# PWM_Controller_Half_Bridge_V2.net
KiCad netlist of a schematic drawn in Altium Designer
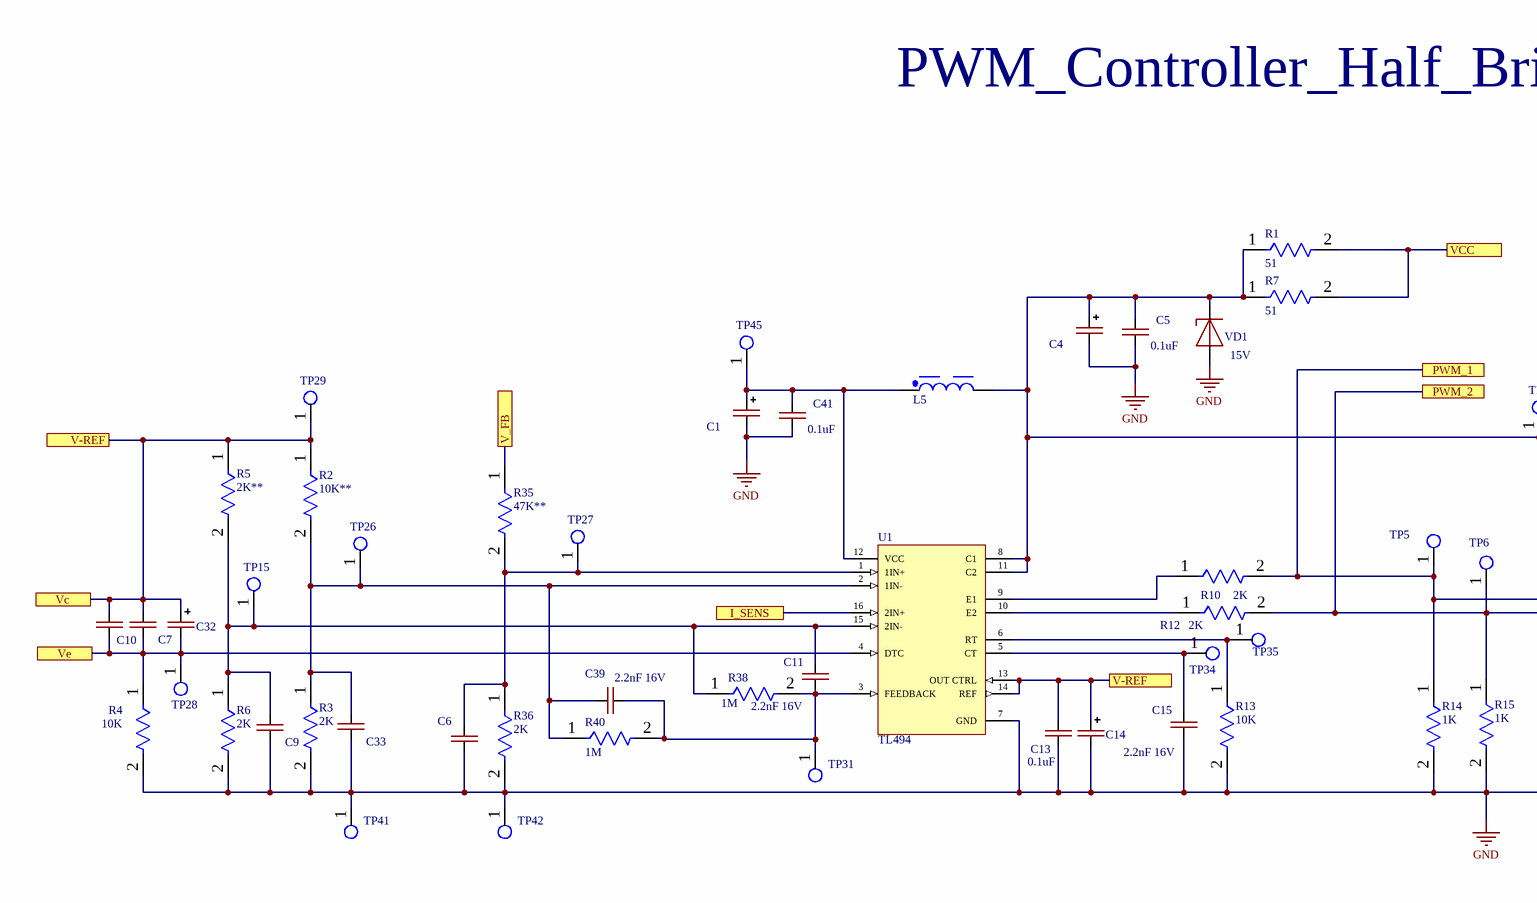
[diagram p0: PWM_Controller_Half_Bridge_V2.SchDoc, left]
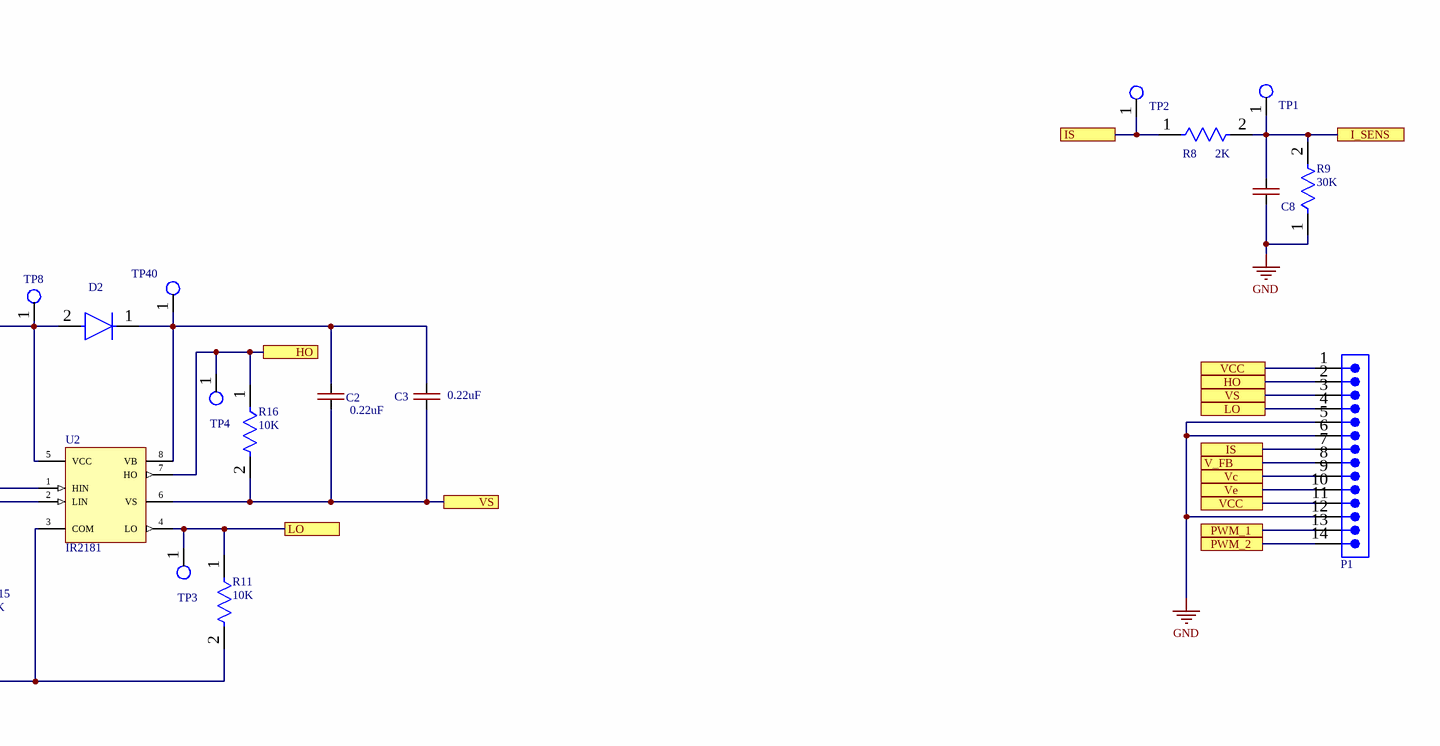
[diagram p1: PWM_Controller_Half_Bridge_V2.SchDoc, right]

(export (version "E")
  (design (tool "Eeschema 10.0.6"))
  (components
    (comp (ref "C1")
      (value "CAP-POLAR")
      (footprint "SIZE_EEE")
      (libsource (lib "PASSIVE_COMPONENTS") (part "CAP-POLAR"))
    )
    (comp (ref "C2")
      (value "0.22uF")
      (footprint "FP-C1210X475K5RACTU-IPC_C")
      (libsource (lib "PASSIVE_COMPONENTS") (part "CAP_1210"))
    )
    (comp (ref "C3")
      (value "0.22uF")
      (footprint "FP-C1210X475K5RACTU-IPC_C")
      (libsource (lib "PASSIVE_COMPONENTS") (part "CAP_1210"))
    )
    (comp (ref "C4")
      (value "CAP-POLAR")
      (footprint "SIZE_EEE")
      (libsource (lib "PASSIVE_COMPONENTS") (part "CAP-POLAR"))
    )
    (comp (ref "C5")
      (value "0.1uF")
      (footprint "CAP-0805")
      (libsource (lib "PASSIVE_COMPONENTS") (part "CAP-NON-POLAR"))
    )
    (comp (ref "C6")
      (value "CAP-NON-POLAR")
      (footprint "CAP-0805")
      (libsource (lib "PASSIVE_COMPONENTS") (part "CAP-NON-POLAR"))
    )
    (comp (ref "C7")
      (value "CAP-NON-POLAR")
      (footprint "CAP-0805")
      (libsource (lib "PASSIVE_COMPONENTS") (part "CAP-NON-POLAR"))
    )
    (comp (ref "C8")
      (value "CAP-NON-POLAR")
      (footprint "CAP-0805")
      (libsource (lib "PASSIVE_COMPONENTS") (part "CAP-NON-POLAR"))
    )
    (comp (ref "C9")
      (value "CAP-NON-POLAR")
      (footprint "CAP-0805")
      (libsource (lib "PASSIVE_COMPONENTS") (part "CAP-NON-POLAR"))
    )
    (comp (ref "C10")
      (value "CAP-NON-POLAR")
      (footprint "CAP-0805")
      (libsource (lib "PASSIVE_COMPONENTS") (part "CAP-NON-POLAR"))
    )
    (comp (ref "C11")
      (value "2.2nF 16V")
      (footprint "CAP-0805")
      (libsource (lib "PASSIVE_COMPONENTS") (part "CAP-NON-POLAR"))
    )
    (comp (ref "C13")
      (value "0.1uF")
      (footprint "CAP-0805")
      (libsource (lib "PASSIVE_COMPONENTS") (part "CAP-NON-POLAR"))
    )
    (comp (ref "C14")
      (value "CAP-POLAR")
      (footprint "CAP-TAN-D")
      (libsource (lib "PASSIVE_COMPONENTS") (part "CAP-POLAR"))
    )
    (comp (ref "C15")
      (value "2.2nF 16V")
      (footprint "CAP-0805")
      (libsource (lib "PASSIVE_COMPONENTS") (part "CAP-NON-POLAR"))
    )
    (comp (ref "C32")
      (value "CAP-POLAR")
      (footprint "CAP-TAN-D")
      (libsource (lib "PASSIVE_COMPONENTS") (part "CAP-POLAR"))
    )
    (comp (ref "C33")
      (value "CAP-NON-POLAR")
      (footprint "CAP-0805")
      (libsource (lib "PASSIVE_COMPONENTS") (part "CAP-NON-POLAR"))
    )
    (comp (ref "C39")
      (value "2.2nF 16V")
      (footprint "CAP-0805")
      (libsource (lib "PASSIVE_COMPONENTS") (part "CAP-NON-POLAR"))
    )
    (comp (ref "C41")
      (value "0.1uF")
      (footprint "CAP-0805")
      (libsource (lib "PASSIVE_COMPONENTS") (part "CAP-NON-POLAR"))
    )
    (comp (ref "D2") (value "US1G") (footprint "DO-214AA") (libsource (lib "Diodes") (part "US1G")))
    (comp (ref "L5")
      (value "47µH, 1.17A")
      (footprint "WE-PD2_7850")
      (description "WE-PD2 SMT Power Inductor, size 7850, 47µH, 1.17A, 0.18Ω")
      (fields
        (field (name "MANUFACTURER PART NUMBER") "744775147")
        (field (name "MANUFACTURER") "Wurth Elektronik")
      )
      (libsource (lib "WE-PD2 (rev22d)") (part "744775147"))
    )
    (comp (ref "P1")
      (value "61301411021")
      (footprint "61301411021")
      (description "WR-PHD Pin Header, THT, Angled, pitch 2.54mm, 1 Row, 14P")
      (fields (field (name "MANUFACTURER") "Wurth Elektronik"))
      (libsource (lib "Altium_WR-PHD (rev22b)") (part "61301411021"))
    )
    (comp (ref "R1")
      (value "51")
      (footprint "FP-RMCF1210-MFG")
      (description "51Ω ±5% 0.5W 1210 Thick Film Chip Resistor AEC-Q200 compliant")
      (fields (field (name "TOLERANCE") "5%"))
      (libsource (lib "Altium Content Vault") (part "1029c3af85768c4190bb7ad29bc67b5"))
    )
    (comp (ref "R2")
      (value "10K**")
      (footprint "RES-0805")
      (description "10K")
      (libsource (lib "PASSIVE_COMPONENTS") (part "RES-CONST"))
    )
    (comp (ref "R3")
      (value "2K")
      (footprint "RES-0805")
      (libsource (lib "PASSIVE_COMPONENTS") (part "RES-CONST"))
    )
    (comp (ref "R4")
      (value "10K")
      (footprint "RES-0805")
      (libsource (lib "PASSIVE_COMPONENTS") (part "RES-CONST"))
    )
    (comp (ref "R5")
      (value "2K**")
      (footprint "RES-0805")
      (description "2K")
      (libsource (lib "PASSIVE_COMPONENTS") (part "RES-CONST"))
    )
    (comp (ref "R6")
      (value "2K")
      (footprint "RES-0805")
      (libsource (lib "PASSIVE_COMPONENTS") (part "RES-CONST"))
    )
    (comp (ref "R7")
      (value "51")
      (footprint "FP-RMCF1210-MFG")
      (description "51Ω ±5% 0.5W 1210 Thick Film Chip Resistor AEC-Q200 compliant")
      (fields (field (name "TOLERANCE") "5%"))
      (libsource (lib "Altium Content Vault") (part "1029c3af85768c4190bb7ad29bc67b5"))
    )
    (comp (ref "R8")
      (value "2K")
      (footprint "RES-0805")
      (libsource (lib "PASSIVE_COMPONENTS") (part "RES-CONST"))
    )
    (comp (ref "R9")
      (value "30K")
      (footprint "RES-0805")
      (libsource (lib "PASSIVE_COMPONENTS") (part "RES-CONST"))
    )
    (comp (ref "R10")
      (value "2K")
      (footprint "RES-0805")
      (libsource (lib "PASSIVE_COMPONENTS") (part "RES-CONST"))
    )
    (comp (ref "R11")
      (value "10K")
      (footprint "RES-0805")
      (libsource (lib "PASSIVE_COMPONENTS") (part "RES-CONST"))
    )
    (comp (ref "R12")
      (value "2K")
      (footprint "RES-0805")
      (libsource (lib "PASSIVE_COMPONENTS") (part "RES-CONST"))
    )
    (comp (ref "R13")
      (value "10K")
      (footprint "RES-0805")
      (libsource (lib "PASSIVE_COMPONENTS") (part "RES-CONST"))
    )
    (comp (ref "R14")
      (value "1K")
      (footprint "RES-0805")
      (libsource (lib "PASSIVE_COMPONENTS") (part "RES-CONST"))
    )
    (comp (ref "R15")
      (value "1K")
      (footprint "RES-0805")
      (libsource (lib "PASSIVE_COMPONENTS") (part "RES-CONST"))
    )
    (comp (ref "R16")
      (value "10K")
      (footprint "RES-0805")
      (libsource (lib "PASSIVE_COMPONENTS") (part "RES-CONST"))
    )
    (comp (ref "R35")
      (value "47K**")
      (footprint "RES-0805")
      (description "47K")
      (libsource (lib "PASSIVE_COMPONENTS") (part "RES-CONST"))
    )
    (comp (ref "R36")
      (value "2K")
      (footprint "RES-0805")
      (libsource (lib "PASSIVE_COMPONENTS") (part "RES-CONST"))
    )
    (comp (ref "R38")
      (value "1M")
      (footprint "RES-0805")
      (libsource (lib "PASSIVE_COMPONENTS") (part "RES-CONST"))
    )
    (comp (ref "R40")
      (value "1M")
      (footprint "RES-0805")
      (libsource (lib "PASSIVE_COMPONENTS") (part "RES-CONST"))
    )
    (comp (ref "TP1")
      (value "~")
      (footprint "Test_Point")
      (description "Test_Point")
      (libsource (lib "Connectors") (part "TP_PCB?"))
    )
    (comp (ref "TP2")
      (value "~")
      (footprint "Test_Point")
      (description "Test_Point")
      (libsource (lib "Connectors") (part "TP_PCB?"))
    )
    (comp (ref "TP3")
      (value "~")
      (footprint "Test_Point")
      (description "Test_Point")
      (libsource (lib "Connectors") (part "TP_PCB?"))
    )
    (comp (ref "TP4")
      (value "~")
      (footprint "Test_Point")
      (description "Test_Point")
      (libsource (lib "Connectors") (part "TP_PCB?"))
    )
    (comp (ref "TP5")
      (value "~")
      (footprint "Test_Point")
      (description "Test_Point")
      (libsource (lib "Connectors") (part "TP_PCB?"))
    )
    (comp (ref "TP6")
      (value "~")
      (footprint "Test_Point")
      (description "Test_Point")
      (libsource (lib "Connectors") (part "TP_PCB?"))
    )
    (comp (ref "TP8")
      (value "~")
      (footprint "Test_Point")
      (description "Test_Point")
      (libsource (lib "Connectors") (part "TP_PCB?"))
    )
    (comp (ref "TP15")
      (value "~")
      (footprint "Test_Point")
      (description "Test_Point")
      (libsource (lib "Connectors") (part "TP_PCB?"))
    )
    (comp (ref "TP26")
      (value "~")
      (footprint "Test_Point")
      (description "Test_Point")
      (libsource (lib "Connectors") (part "TP_PCB?"))
    )
    (comp (ref "TP27")
      (value "~")
      (footprint "Test_Point")
      (description "Test_Point")
      (libsource (lib "Connectors") (part "TP_PCB?"))
    )
    (comp (ref "TP28")
      (value "~")
      (footprint "Test_Point")
      (description "Test_Point")
      (libsource (lib "Connectors") (part "TP_PCB?"))
    )
    (comp (ref "TP29")
      (value "~")
      (footprint "Test_Point")
      (description "Test_Point")
      (libsource (lib "Connectors") (part "TP_PCB?"))
    )
    (comp (ref "TP31")
      (value "~")
      (footprint "Test_Point")
      (description "Test_Point")
      (libsource (lib "Connectors") (part "TP_PCB?"))
    )
    (comp (ref "TP34")
      (value "~")
      (footprint "Test_Point")
      (description "Test_Point")
      (libsource (lib "Connectors") (part "TP_PCB?"))
    )
    (comp (ref "TP35")
      (value "~")
      (footprint "Test_Point")
      (description "Test_Point")
      (libsource (lib "Connectors") (part "TP_PCB?"))
    )
    (comp (ref "TP40")
      (value "~")
      (footprint "Test_Point")
      (description "Test_Point")
      (libsource (lib "Connectors") (part "TP_PCB?"))
    )
    (comp (ref "TP41")
      (value "~")
      (footprint "Test_Point")
      (description "Test_Point")
      (libsource (lib "Connectors") (part "TP_PCB?"))
    )
    (comp (ref "TP42")
      (value "~")
      (footprint "Test_Point")
      (description "Test_Point")
      (libsource (lib "Connectors") (part "TP_PCB?"))
    )
    (comp (ref "TP45")
      (value "~")
      (footprint "Test_Point")
      (description "Test_Point")
      (libsource (lib "Connectors") (part "TP_PCB?"))
    )
    (comp (ref "U1")
      (value "TL494")
      (footprint "SOIC-16-M")
      (description "TL494 Pwm controller")
      (libsource (lib "Integrated_Circuts") (part "TL494"))
    )
    (comp (ref "U2")
      (value "IR2181")
      (footprint "SO8-150")
      (description "IR2181 Driver")
      (libsource (lib "Integrated_Circuts") (part "IR2181"))
    )
    (comp (ref "VD1") (value "15V") (footprint "DO-017AA") (libsource (lib "Diodes") (part "ZENER")))
  )
  (nets
    (net (code "1") (name "/HO") (class "Default")
      (node (ref "P1") (pin "2") (pinfunction "2_2") (pintype "passive"))
      (node (ref "R16") (pin "1") (pinfunction "1_1") (pintype "passive"))
      (node (ref "TP4") (pin "1") (pinfunction "G9_1") (pintype "passive"))
      (node (ref "U2") (pin "7") (pinfunction "HO_7") (pintype "output"))
    )
    (net (code "2") (name "/IS") (class "Default")
      (node (ref "P1") (pin "7") (pinfunction "7_7") (pintype "passive"))
      (node (ref "R8") (pin "1") (pinfunction "1_1") (pintype "passive"))
      (node (ref "TP2") (pin "1") (pinfunction "G9_1") (pintype "passive"))
    )
    (net (code "3") (name "/I_SENS") (class "Default")
      (node (ref "C8") (pin "2") (pinfunction "2_2") (pintype "passive"))
      (node (ref "R8") (pin "2") (pinfunction "2_2") (pintype "passive"))
      (node (ref "R9") (pin "2") (pinfunction "2_2") (pintype "passive"))
      (node (ref "TP1") (pin "1") (pinfunction "G9_1") (pintype "passive"))
      (node (ref "U1") (pin "16") (pinfunction "2IN+_16") (pintype "input"))
    )
    (net (code "4") (name "/LO") (class "Default")
      (node (ref "P1") (pin "4") (pinfunction "4_4") (pintype "passive"))
      (node (ref "R11") (pin "1") (pinfunction "1_1") (pintype "passive"))
      (node (ref "TP3") (pin "1") (pinfunction "G9_1") (pintype "passive"))
      (node (ref "U2") (pin "4") (pinfunction "LO_4") (pintype "output"))
    )
    (net (code "5") (name "/PWM_1") (class "Default")
      (node (ref "P1") (pin "13") (pinfunction "13_13") (pintype "passive"))
      (node (ref "R10") (pin "2") (pinfunction "2_2") (pintype "passive"))
      (node (ref "R14") (pin "1") (pinfunction "1_1") (pintype "passive"))
      (node (ref "TP5") (pin "1") (pinfunction "G9_1") (pintype "passive"))
      (node (ref "U2") (pin "1") (pinfunction "HIN_1") (pintype "input"))
    )
    (net (code "6") (name "/PWM_2") (class "Default")
      (node (ref "P1") (pin "14") (pinfunction "14_14") (pintype "passive"))
      (node (ref "R12") (pin "2") (pinfunction "2_2") (pintype "passive"))
      (node (ref "R15") (pin "1") (pinfunction "1_1") (pintype "passive"))
      (node (ref "TP6") (pin "1") (pinfunction "G9_1") (pintype "passive"))
      (node (ref "U2") (pin "2") (pinfunction "LIN_2") (pintype "input"))
    )
    (net (code "7") (name "/V-REF") (class "Default")
      (node (ref "C10") (pin "2") (pinfunction "2_2") (pintype "passive"))
      (node (ref "C13") (pin "2") (pinfunction "2_2") (pintype "passive"))
      (node (ref "C14") (pin "1") (pinfunction "+_1") (pintype "passive"))
      (node (ref "C32") (pin "1") (pinfunction "+_1") (pintype "passive"))
      (node (ref "C7") (pin "2") (pinfunction "2_2") (pintype "passive"))
      (node (ref "P1") (pin "9") (pinfunction "9_9") (pintype "passive"))
      (node (ref "R2") (pin "1") (pinfunction "1_1") (pintype "passive"))
      (node (ref "R5") (pin "1") (pinfunction "1_1") (pintype "passive"))
      (node (ref "TP29") (pin "1") (pinfunction "G9_1") (pintype "passive"))
      (node (ref "U1") (pin "13") (pinfunction "OUT_CTRL_13") (pintype "input"))
      (node (ref "U1") (pin "14") (pinfunction "REF_14") (pintype "output"))
    )
    (net (code "8") (name "/VCC") (class "Default")
      (node (ref "P1") (pin "1") (pinfunction "1_1") (pintype "passive"))
      (node (ref "P1") (pin "11") (pinfunction "11_11") (pintype "passive"))
      (node (ref "R1") (pin "2") (pinfunction "2_2") (pintype "passive"))
      (node (ref "R7") (pin "2") (pinfunction "2_2") (pintype "passive"))
    )
    (net (code "9") (name "/VS") (class "Default")
      (node (ref "C2") (pin "1") (pinfunction "1_1") (pintype "passive"))
      (node (ref "C3") (pin "1") (pinfunction "1_1") (pintype "passive"))
      (node (ref "P1") (pin "3") (pinfunction "3_3") (pintype "passive"))
      (node (ref "R16") (pin "2") (pinfunction "2_2") (pintype "passive"))
      (node (ref "U2") (pin "6") (pinfunction "VS_6") (pintype "power_in"))
    )
    (net (code "10") (name "/V_FB") (class "Default")
      (node (ref "P1") (pin "8") (pinfunction "8_8") (pintype "passive"))
      (node (ref "R35") (pin "1") (pinfunction "1_1") (pintype "passive"))
    )
    (net (code "11") (name "/Ve") (class "Default")
      (node (ref "C10") (pin "1") (pinfunction "1_1") (pintype "passive"))
      (node (ref "C32") (pin "2") (pinfunction "-_2") (pintype "passive"))
      (node (ref "C7") (pin "1") (pinfunction "1_1") (pintype "passive"))
      (node (ref "P1") (pin "10") (pinfunction "10_10") (pintype "passive"))
      (node (ref "R4") (pin "1") (pinfunction "1_1") (pintype "passive"))
      (node (ref "TP28") (pin "1") (pinfunction "G9_1") (pintype "passive"))
      (node (ref "U1") (pin "4") (pinfunction "DTC_4") (pintype "input"))
    )
    (net (code "12") (name "GND") (class "Default")
      (node (ref "C1") (pin "2") (pinfunction "-_2") (pintype "passive"))
      (node (ref "C13") (pin "1") (pinfunction "1_1") (pintype "passive"))
      (node (ref "C14") (pin "2") (pinfunction "-_2") (pintype "passive"))
      (node (ref "C15") (pin "1") (pinfunction "1_1") (pintype "passive"))
      (node (ref "C33") (pin "1") (pinfunction "1_1") (pintype "passive"))
      (node (ref "C4") (pin "2") (pinfunction "-_2") (pintype "passive"))
      (node (ref "C41") (pin "1") (pinfunction "1_1") (pintype "passive"))
      (node (ref "C5") (pin "1") (pinfunction "1_1") (pintype "passive"))
      (node (ref "C6") (pin "1") (pinfunction "1_1") (pintype "passive"))
      (node (ref "C8") (pin "1") (pinfunction "1_1") (pintype "passive"))
      (node (ref "C9") (pin "1") (pinfunction "1_1") (pintype "passive"))
      (node (ref "P1") (pin "12") (pinfunction "12_12") (pintype "passive"))
      (node (ref "P1") (pin "5") (pinfunction "5_5") (pintype "passive"))
      (node (ref "P1") (pin "6") (pinfunction "6_6") (pintype "passive"))
      (node (ref "R11") (pin "2") (pinfunction "2_2") (pintype "passive"))
      (node (ref "R13") (pin "2") (pinfunction "2_2") (pintype "passive"))
      (node (ref "R14") (pin "2") (pinfunction "2_2") (pintype "passive"))
      (node (ref "R15") (pin "2") (pinfunction "2_2") (pintype "passive"))
      (node (ref "R3") (pin "2") (pinfunction "2_2") (pintype "passive"))
      (node (ref "R36") (pin "2") (pinfunction "2_2") (pintype "passive"))
      (node (ref "R4") (pin "2") (pinfunction "2_2") (pintype "passive"))
      (node (ref "R6") (pin "2") (pinfunction "2_2") (pintype "passive"))
      (node (ref "R9") (pin "1") (pinfunction "1_1") (pintype "passive"))
      (node (ref "TP41") (pin "1") (pinfunction "G9_1") (pintype "passive"))
      (node (ref "TP42") (pin "1") (pinfunction "G9_1") (pintype "passive"))
      (node (ref "U1") (pin "7") (pinfunction "GND_7") (pintype "power_in"))
      (node (ref "U2") (pin "3") (pinfunction "COM_3") (pintype "passive"))
      (node (ref "VD1") (pin "2") (pinfunction "A_2") (pintype "passive"))
    )
    (net (code "13") (name "Net-(C1-+)") (class "Default")
      (node (ref "C1") (pin "1") (pinfunction "+_1") (pintype "passive"))
      (node (ref "C41") (pin "2") (pinfunction "2_2") (pintype "passive"))
      (node (ref "L5") (pin "1") (pinfunction "1_1") (pintype "passive"))
      (node (ref "TP45") (pin "1") (pinfunction "G9_1") (pintype "passive"))
      (node (ref "U1") (pin "12") (pinfunction "VCC_12") (pintype "power_in"))
    )
    (net (code "14") (name "Net-(C4-+)") (class "Default")
      (node (ref "C4") (pin "1") (pinfunction "+_1") (pintype "passive"))
      (node (ref "C5") (pin "2") (pinfunction "2_2") (pintype "passive"))
      (node (ref "D2") (pin "2") (pinfunction "A_2") (pintype "passive"))
      (node (ref "L5") (pin "2") (pinfunction "2_2") (pintype "passive"))
      (node (ref "R1") (pin "1") (pinfunction "1_1") (pintype "passive"))
      (node (ref "R7") (pin "1") (pinfunction "1_1") (pintype "passive"))
      (node (ref "TP8") (pin "1") (pinfunction "G9_1") (pintype "passive"))
      (node (ref "U1") (pin "11") (pinfunction "C2_11") (pintype "passive"))
      (node (ref "U1") (pin "8") (pinfunction "C1_8") (pintype "passive"))
      (node (ref "U2") (pin "5") (pinfunction "VCC_5") (pintype "power_in"))
      (node (ref "VD1") (pin "1") (pinfunction "C_1") (pintype "passive"))
    )
    (net (code "15") (name "Net-(D2-C)") (class "Default")
      (node (ref "C2") (pin "2") (pinfunction "2_2") (pintype "passive"))
      (node (ref "C3") (pin "2") (pinfunction "2_2") (pintype "passive"))
      (node (ref "D2") (pin "1") (pinfunction "C_1") (pintype "passive"))
      (node (ref "TP40") (pin "1") (pinfunction "G9_1") (pintype "passive"))
      (node (ref "U2") (pin "8") (pinfunction "VB_8") (pintype "power_in"))
    )
    (net (code "16") (name "Net-(TP15-G9)") (class "Default")
      (node (ref "C11") (pin "2") (pinfunction "2_2") (pintype "passive"))
      (node (ref "C9") (pin "2") (pinfunction "2_2") (pintype "passive"))
      (node (ref "R38") (pin "1") (pinfunction "1_1") (pintype "passive"))
      (node (ref "R5") (pin "2") (pinfunction "2_2") (pintype "passive"))
      (node (ref "R6") (pin "1") (pinfunction "1_1") (pintype "passive"))
      (node (ref "TP15") (pin "1") (pinfunction "G9_1") (pintype "passive"))
      (node (ref "U1") (pin "15") (pinfunction "2IN-_15") (pintype "input"))
    )
    (net (code "17") (name "Net-(TP26-G9)") (class "Default")
      (node (ref "C33") (pin "2") (pinfunction "2_2") (pintype "passive"))
      (node (ref "C39") (pin "2") (pinfunction "2_2") (pintype "passive"))
      (node (ref "R2") (pin "2") (pinfunction "2_2") (pintype "passive"))
      (node (ref "R3") (pin "1") (pinfunction "1_1") (pintype "passive"))
      (node (ref "R40") (pin "1") (pinfunction "1_1") (pintype "passive"))
      (node (ref "TP26") (pin "1") (pinfunction "G9_1") (pintype "passive"))
      (node (ref "U1") (pin "2") (pinfunction "1IN-_2") (pintype "input"))
    )
    (net (code "18") (name "Net-(TP27-G9)") (class "Default")
      (node (ref "C6") (pin "2") (pinfunction "2_2") (pintype "passive"))
      (node (ref "R35") (pin "2") (pinfunction "2_2") (pintype "passive"))
      (node (ref "R36") (pin "1") (pinfunction "1_1") (pintype "passive"))
      (node (ref "TP27") (pin "1") (pinfunction "G9_1") (pintype "passive"))
      (node (ref "U1") (pin "1") (pinfunction "1IN+_1") (pintype "input"))
    )
    (net (code "19") (name "Net-(TP31-G9)") (class "Default")
      (node (ref "C11") (pin "1") (pinfunction "1_1") (pintype "passive"))
      (node (ref "C39") (pin "1") (pinfunction "1_1") (pintype "passive"))
      (node (ref "R38") (pin "2") (pinfunction "2_2") (pintype "passive"))
      (node (ref "R40") (pin "2") (pinfunction "2_2") (pintype "passive"))
      (node (ref "TP31") (pin "1") (pinfunction "G9_1") (pintype "passive"))
      (node (ref "U1") (pin "3") (pinfunction "FEEDBACK_3") (pintype "input"))
    )
    (net (code "20") (name "Net-(TP34-G9)") (class "Default")
      (node (ref "C15") (pin "2") (pinfunction "2_2") (pintype "passive"))
      (node (ref "TP34") (pin "1") (pinfunction "G9_1") (pintype "passive"))
      (node (ref "U1") (pin "5") (pinfunction "CT_5") (pintype "passive"))
    )
    (net (code "21") (name "Net-(TP35-G9)") (class "Default")
      (node (ref "R13") (pin "1") (pinfunction "1_1") (pintype "passive"))
      (node (ref "TP35") (pin "1") (pinfunction "G9_1") (pintype "passive"))
      (node (ref "U1") (pin "6") (pinfunction "RT_6") (pintype "passive"))
    )
    (net (code "22") (name "Net-(U1-E1)") (class "Default")
      (node (ref "R10") (pin "1") (pinfunction "1_1") (pintype "passive"))
      (node (ref "U1") (pin "9") (pinfunction "E1_9") (pintype "passive"))
    )
    (net (code "23") (name "Net-(U1-E2)") (class "Default")
      (node (ref "R12") (pin "1") (pinfunction "1_1") (pintype "passive"))
      (node (ref "U1") (pin "10") (pinfunction "E2_10") (pintype "passive"))
    )
  )
)
